# test-1.net
KiCad netlist of a schematic drawn in EAGLE
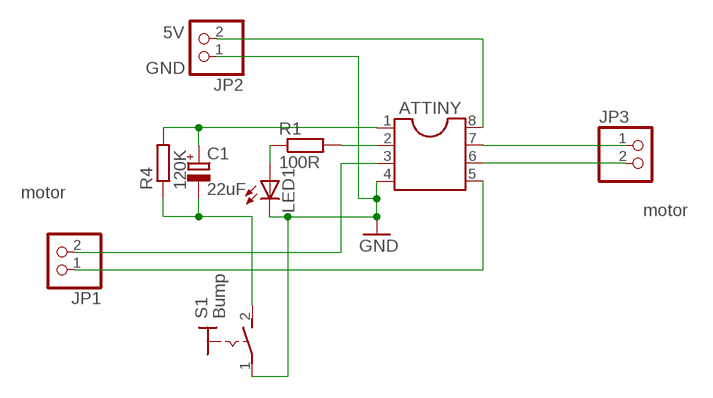
[diagram p0: schematic, sheet 1]

(export (version "E")
  (design (tool "Eeschema 10.0.6"))
  (components
    (comp (ref "ATTINY")
      (value "DIL8")
      (footprint "eagle-import:DIL08")
      (libsource (lib "eagle-import") (part "DIL8"))
    )
    (comp (ref "C1")
      (value "22uF")
      (footprint "eagle-import:E3,5-8")
      (libsource (lib "eagle-import") (part "CPOL-EUE3.5-8"))
    )
    (comp (ref "JP1")
      (value "PINHD-1X2")
      (footprint "eagle-import:1X02")
      (libsource (lib "eagle-import") (part "PINHD-1X2"))
    )
    (comp (ref "JP2")
      (value "PINHD-1X2")
      (footprint "eagle-import:1X02")
      (libsource (lib "eagle-import") (part "PINHD-1X2"))
    )
    (comp (ref "JP3")
      (value "PINHD-1X2")
      (footprint "eagle-import:1X02")
      (libsource (lib "eagle-import") (part "PINHD-1X2"))
    )
    (comp (ref "LED1")
      (value "LED3MM")
      (footprint "eagle-import:LED3MM")
      (libsource (lib "eagle-import") (part "LED3MM"))
    )
    (comp (ref "R1")
      (value "100R")
      (footprint "eagle-import:0204_7")
      (libsource (lib "eagle-import") (part "R-EU_0204/7"))
    )
    (comp (ref "R4")
      (value "120K")
      (footprint "eagle-import:0204_7")
      (libsource (lib "eagle-import") (part "R-EU_0204/7"))
    )
    (comp (ref "S1")
      (value "Bump")
      (footprint "eagle-import:MS243")
      (libsource (lib "eagle-import") (part "MS243"))
    )
  )
  (nets
    (net (code "1") (name "GND") (class "Default")
      (node (ref "ATTINY") (pin "4") (pinfunction "4_4") (pintype "passive"))
      (node (ref "JP2") (pin "1") (pinfunction "1_1") (pintype "passive"))
      (node (ref "LED1") (pin "K") (pinfunction "C_K") (pintype "passive"))
      (node (ref "S1") (pin "1") (pinfunction "P_1") (pintype "passive"))
    )
    (net (code "2") (name "Net-(ATTINY-Pad1)") (class "Default")
      (node (ref "ATTINY") (pin "1") (pinfunction "1_1") (pintype "passive"))
      (node (ref "C1") (pin "+") (pinfunction "+_+") (pintype "passive"))
      (node (ref "R4") (pin "2") (pinfunction "2_2") (pintype "passive"))
    )
    (net (code "3") (name "Net-(ATTINY-Pad2)") (class "Default")
      (node (ref "ATTINY") (pin "2") (pinfunction "2_2") (pintype "passive"))
      (node (ref "R1") (pin "2") (pinfunction "2_2") (pintype "passive"))
    )
    (net (code "4") (name "Net-(ATTINY-Pad3)") (class "Default")
      (node (ref "ATTINY") (pin "3") (pinfunction "3_3") (pintype "passive"))
      (node (ref "JP1") (pin "2") (pinfunction "2_2") (pintype "passive"))
    )
    (net (code "5") (name "Net-(ATTINY-Pad5)") (class "Default")
      (node (ref "ATTINY") (pin "5") (pinfunction "5_5") (pintype "passive"))
      (node (ref "JP1") (pin "1") (pinfunction "1_1") (pintype "passive"))
    )
    (net (code "6") (name "Net-(ATTINY-Pad6)") (class "Default")
      (node (ref "ATTINY") (pin "6") (pinfunction "6_6") (pintype "passive"))
      (node (ref "JP3") (pin "2") (pinfunction "2_2") (pintype "passive"))
    )
    (net (code "7") (name "Net-(ATTINY-Pad7)") (class "Default")
      (node (ref "ATTINY") (pin "7") (pinfunction "7_7") (pintype "passive"))
      (node (ref "JP3") (pin "1") (pinfunction "1_1") (pintype "passive"))
    )
    (net (code "8") (name "Net-(ATTINY-Pad8)") (class "Default")
      (node (ref "ATTINY") (pin "8") (pinfunction "8_8") (pintype "passive"))
      (node (ref "JP2") (pin "2") (pinfunction "2_2") (pintype "passive"))
    )
    (net (code "9") (name "Net-(LED1-PadA)") (class "Default")
      (node (ref "LED1") (pin "A") (pinfunction "A_A") (pintype "passive"))
      (node (ref "R1") (pin "1") (pinfunction "1_1") (pintype "passive"))
    )
    (net (code "10") (name "Net-(S1-S)") (class "Default")
      (node (ref "C1") (pin "-") (pinfunction "-_-") (pintype "passive"))
      (node (ref "R4") (pin "1") (pinfunction "1_1") (pintype "passive"))
      (node (ref "S1") (pin "2") (pinfunction "S_2") (pintype "passive"))
    )
  )
)
